# SilentStepStick-TMC2100_v11.net
KiCad netlist of a schematic drawn in EAGLE
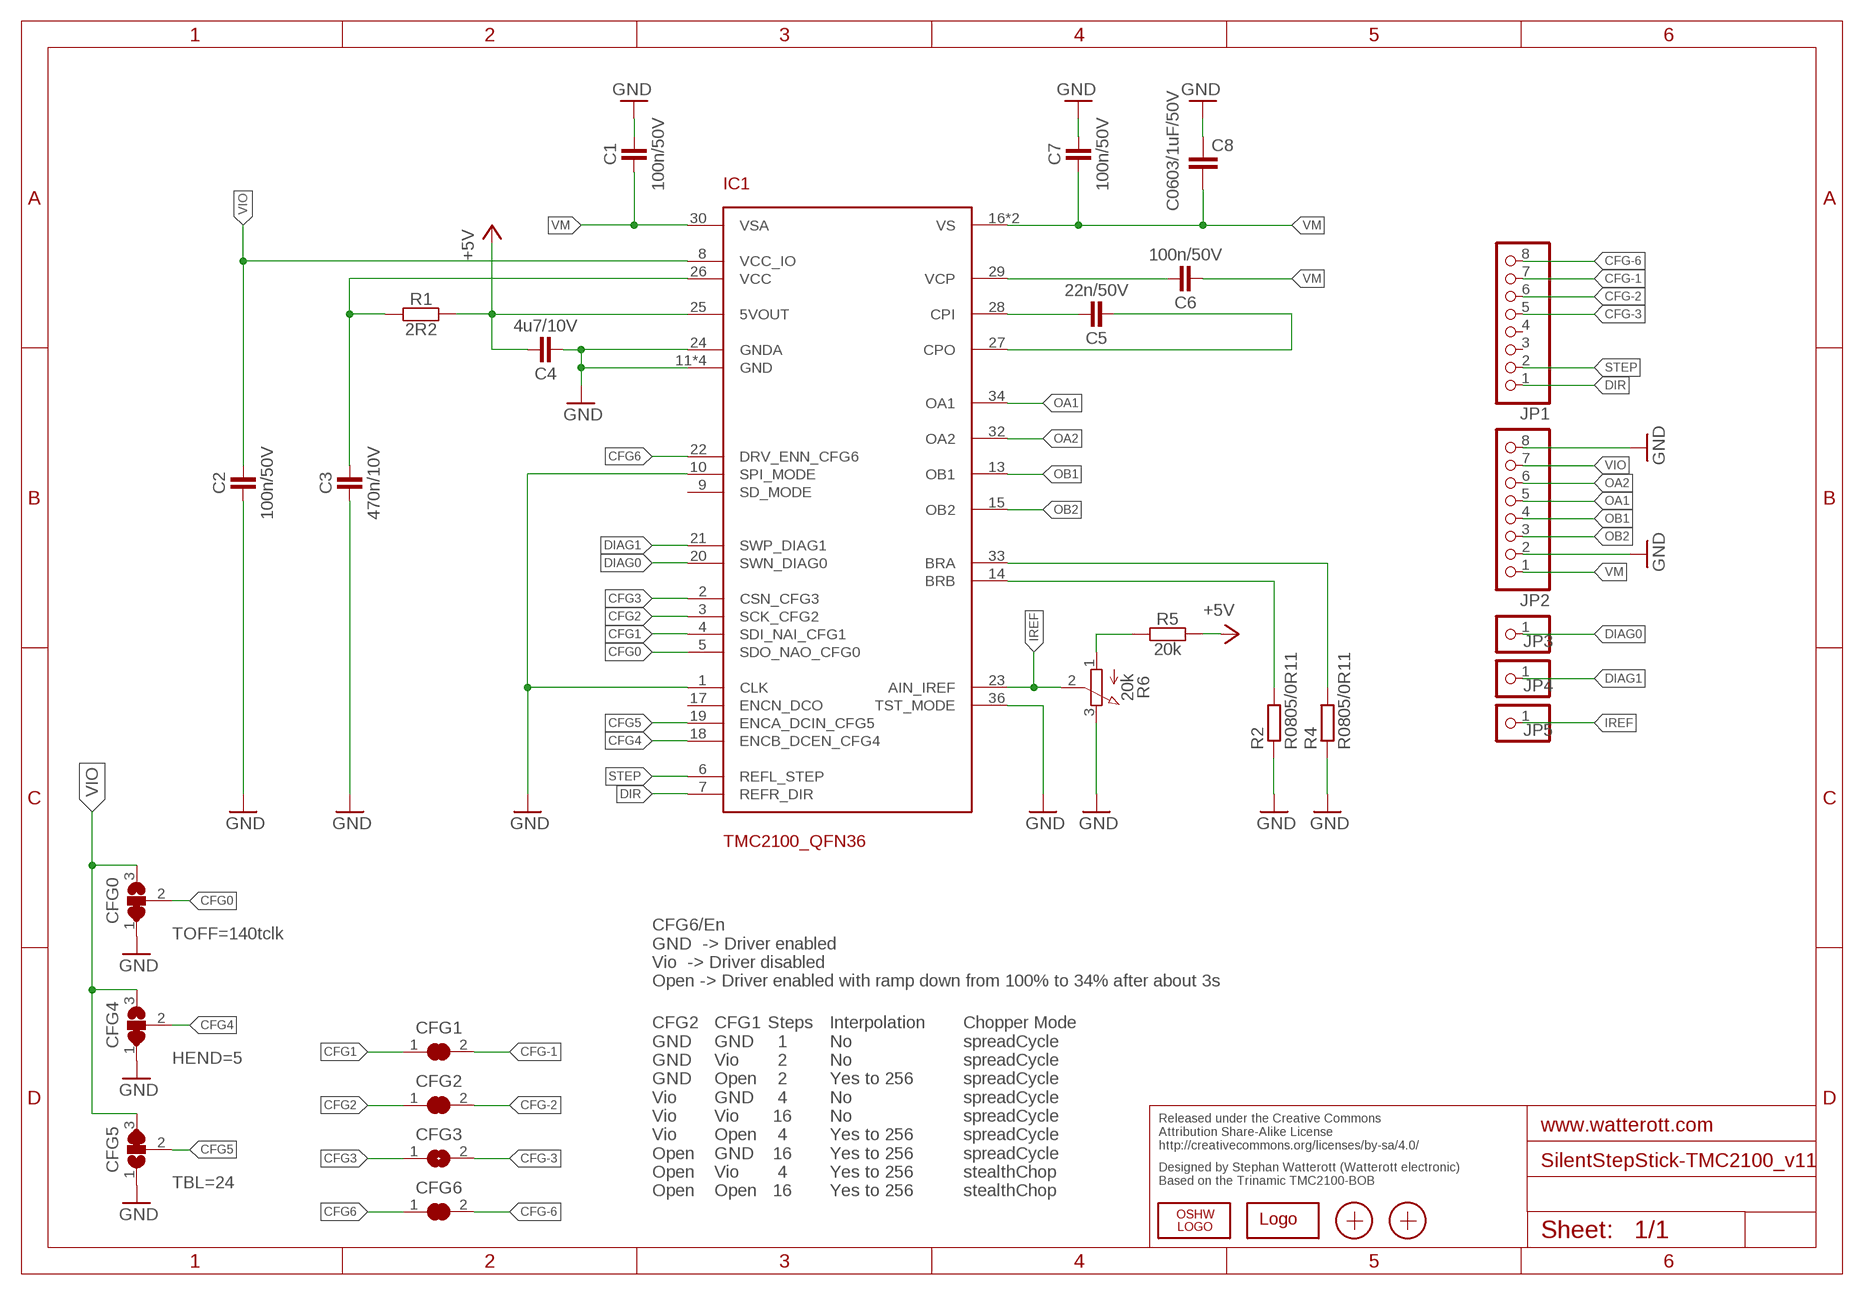
[diagram p0: schematic, sheet 1]

(export (version "E")
  (design (tool "Eeschema 10.0.6"))
  (components
    (comp (ref "C1")
      (value "100n/50V")
      (footprint "eagle-import:R0402")
      (libsource (lib "eagle-import") (part "CAPACITOR-C0402"))
    )
    (comp (ref "C2")
      (value "100n/50V")
      (footprint "eagle-import:R0402")
      (libsource (lib "eagle-import") (part "CAPACITOR-C0402"))
    )
    (comp (ref "C3")
      (value "470n/10V")
      (footprint "eagle-import:R0402")
      (libsource (lib "eagle-import") (part "CAPACITOR-C0402"))
    )
    (comp (ref "C4")
      (value "4u7/10V")
      (footprint "eagle-import:R0402")
      (libsource (lib "eagle-import") (part "CAPACITOR-C0402"))
    )
    (comp (ref "C5")
      (value "22n/50V")
      (footprint "eagle-import:R0402")
      (libsource (lib "eagle-import") (part "CAPACITOR-C0402"))
    )
    (comp (ref "C6")
      (value "100n/50V")
      (footprint "eagle-import:R0402")
      (libsource (lib "eagle-import") (part "CAPACITOR-C0402"))
    )
    (comp (ref "C7")
      (value "100n/50V")
      (footprint "eagle-import:R0402")
      (libsource (lib "eagle-import") (part "CAPACITOR-C0402"))
    )
    (comp (ref "C8")
      (value "C0603/1uF/50V")
      (footprint "eagle-import:C0603")
      (libsource (lib "eagle-import") (part "C-EUC0603"))
    )
    (comp (ref "CFG0")
      (value "JUMPER3-0201")
      (footprint "eagle-import:JUMPER3-0201")
      (libsource (lib "eagle-import") (part "JUMPER3-0201"))
    )
    (comp (ref "CFG1")
      (value "JUMPER2-0201")
      (footprint "eagle-import:JUMPER2-0201")
      (libsource (lib "eagle-import") (part "JUMPER2-0201"))
    )
    (comp (ref "CFG2")
      (value "JUMPER2-0201")
      (footprint "eagle-import:JUMPER2-0201")
      (libsource (lib "eagle-import") (part "JUMPER2-0201"))
    )
    (comp (ref "CFG3")
      (value "JUMPER2-0201")
      (footprint "eagle-import:JUMPER2-0201")
      (libsource (lib "eagle-import") (part "JUMPER2-0201"))
    )
    (comp (ref "CFG4")
      (value "JUMPER3-0201")
      (footprint "eagle-import:JUMPER3-0201")
      (libsource (lib "eagle-import") (part "JUMPER3-0201"))
    )
    (comp (ref "CFG5")
      (value "JUMPER3-0201")
      (footprint "eagle-import:JUMPER3-0201")
      (libsource (lib "eagle-import") (part "JUMPER3-0201"))
    )
    (comp (ref "CFG6")
      (value "JUMPER2-0201")
      (footprint "eagle-import:JUMPER2-0201")
      (libsource (lib "eagle-import") (part "JUMPER2-0201"))
    )
    (comp (ref "IC1")
      (value "TMC2100_QFN36")
      (footprint "eagle-import:QFN36")
      (libsource (lib "eagle-import") (part "TMC2100_QFN36"))
    )
    (comp (ref "JP1")
      (value "PINHD-1X08_2.54-S")
      (footprint "eagle-import:1X08-S")
      (libsource (lib "eagle-import") (part "PINHD-1X08_2.54-S"))
    )
    (comp (ref "JP2")
      (value "PINHD-1X08_2.54-S")
      (footprint "eagle-import:1X08-S")
      (libsource (lib "eagle-import") (part "PINHD-1X08_2.54-S"))
    )
    (comp (ref "JP3")
      (value "PINHD-1X1")
      (footprint "eagle-import:1X01")
      (libsource (lib "eagle-import") (part "PINHD-1X1"))
    )
    (comp (ref "JP4")
      (value "PINHD-1X1")
      (footprint "eagle-import:1X01")
      (libsource (lib "eagle-import") (part "PINHD-1X1"))
    )
    (comp (ref "JP5")
      (value "PINHD-1X1")
      (footprint "eagle-import:1X01")
      (libsource (lib "eagle-import") (part "PINHD-1X1"))
    )
    (comp (ref "LOGO1")
      (value "OSHW_LOGOX0070")
      (footprint "eagle-import:OSHW_6X70")
      (libsource (lib "eagle-import") (part "OSHW_LOGOX0070"))
    )
    (comp (ref "LOGO2")
      (value "LOGO-S_PLACE_M")
      (footprint "eagle-import:SPARK_TPLACE_M")
      (libsource (lib "eagle-import") (part "LOGO-S_PLACE_M"))
    )
    (comp (ref "R1")
      (value "2R2")
      (footprint "eagle-import:R0402")
      (libsource (lib "eagle-import") (part "RESISTOR-R0402"))
    )
    (comp (ref "R2")
      (value "R0805/0R11")
      (footprint "eagle-import:M0805")
      (libsource (lib "eagle-import") (part "R-EU_M0805"))
    )
    (comp (ref "R4")
      (value "R0805/0R11")
      (footprint "eagle-import:M0805")
      (libsource (lib "eagle-import") (part "R-EU_M0805"))
    )
    (comp (ref "R5")
      (value "20k")
      (footprint "eagle-import:R0402")
      (libsource (lib "eagle-import") (part "RESISTOR-R0402"))
    )
    (comp (ref "R6")
      (value "20k")
      (footprint "eagle-import:POT_EVM3R")
      (libsource (lib "eagle-import") (part "POTEVM3R"))
    )
    (comp (ref "X1")
      (value "PASSER-07")
      (footprint "eagle-import:PASSER_07MM")
      (libsource (lib "eagle-import") (part "PASSER-07"))
    )
    (comp (ref "X2")
      (value "PASSER-07")
      (footprint "eagle-import:PASSER_07MM")
      (libsource (lib "eagle-import") (part "PASSER-07"))
    )
  )
  (nets
    (net (code "1") (name "+5V") (class "Default")
      (node (ref "C4") (pin "2") (pinfunction "2_2") (pintype "passive"))
      (node (ref "IC1") (pin "25") (pinfunction "5VOUT_25") (pintype "bidirectional"))
      (node (ref "R1") (pin "2") (pinfunction "2_2") (pintype "passive"))
      (node (ref "R5") (pin "2") (pinfunction "2_2") (pintype "passive"))
    )
    (net (code "2") (name "CFG-1") (class "Default")
      (node (ref "CFG1") (pin "2") (pinfunction "2_2") (pintype "passive"))
      (node (ref "JP1") (pin "7") (pinfunction "7_7") (pintype "passive"))
    )
    (net (code "3") (name "CFG-2") (class "Default")
      (node (ref "CFG2") (pin "2") (pinfunction "2_2") (pintype "passive"))
      (node (ref "JP1") (pin "6") (pinfunction "6_6") (pintype "passive"))
    )
    (net (code "4") (name "CFG-3") (class "Default")
      (node (ref "CFG3") (pin "2") (pinfunction "2_2") (pintype "passive"))
      (node (ref "JP1") (pin "5") (pinfunction "5_5") (pintype "passive"))
    )
    (net (code "5") (name "CFG-6") (class "Default")
      (node (ref "CFG6") (pin "2") (pinfunction "2_2") (pintype "passive"))
      (node (ref "JP1") (pin "8") (pinfunction "8_8") (pintype "passive"))
    )
    (net (code "6") (name "CFG0") (class "Default")
      (node (ref "CFG0") (pin "2") (pinfunction "2_2") (pintype "passive"))
      (node (ref "IC1") (pin "5") (pinfunction "SDO_NAO_CFG0_5") (pintype "bidirectional"))
    )
    (net (code "7") (name "CFG1") (class "Default")
      (node (ref "CFG1") (pin "1") (pinfunction "1_1") (pintype "passive"))
      (node (ref "IC1") (pin "4") (pinfunction "SDI_NAI_CFG1_4") (pintype "bidirectional"))
    )
    (net (code "8") (name "CFG2") (class "Default")
      (node (ref "CFG2") (pin "1") (pinfunction "1_1") (pintype "passive"))
      (node (ref "IC1") (pin "3") (pinfunction "SCK_CFG2_3") (pintype "bidirectional"))
    )
    (net (code "9") (name "CFG3") (class "Default")
      (node (ref "CFG3") (pin "1") (pinfunction "1_1") (pintype "passive"))
      (node (ref "IC1") (pin "2") (pinfunction "CSN_CFG3_2") (pintype "bidirectional"))
    )
    (net (code "10") (name "CFG4") (class "Default")
      (node (ref "CFG4") (pin "2") (pinfunction "2_2") (pintype "passive"))
      (node (ref "IC1") (pin "18") (pinfunction "ENCB_DCEN_CFG4_18") (pintype "bidirectional"))
    )
    (net (code "11") (name "CFG5") (class "Default")
      (node (ref "CFG5") (pin "2") (pinfunction "2_2") (pintype "passive"))
      (node (ref "IC1") (pin "19") (pinfunction "ENCA_DCIN_CFG5_19") (pintype "bidirectional"))
    )
    (net (code "12") (name "CFG6") (class "Default")
      (node (ref "CFG6") (pin "1") (pinfunction "1_1") (pintype "passive"))
      (node (ref "IC1") (pin "22") (pinfunction "DRV_ENN_CFG6_22") (pintype "bidirectional"))
    )
    (net (code "13") (name "DIAG0") (class "Default")
      (node (ref "IC1") (pin "20") (pinfunction "SWN_DIAG0_20") (pintype "bidirectional"))
      (node (ref "JP3") (pin "1") (pinfunction "1_1") (pintype "passive"))
    )
    (net (code "14") (name "DIAG1") (class "Default")
      (node (ref "IC1") (pin "21") (pinfunction "SWP_DIAG1_21") (pintype "bidirectional"))
      (node (ref "JP4") (pin "1") (pinfunction "1_1") (pintype "passive"))
    )
    (net (code "15") (name "DIR") (class "Default")
      (node (ref "IC1") (pin "7") (pinfunction "REFR_DIR_7") (pintype "bidirectional"))
      (node (ref "JP1") (pin "1") (pinfunction "1_1") (pintype "passive"))
    )
    (net (code "16") (name "GND") (class "Default")
      (node (ref "C1") (pin "2") (pinfunction "2_2") (pintype "passive"))
      (node (ref "C2") (pin "1") (pinfunction "1_1") (pintype "passive"))
      (node (ref "C3") (pin "1") (pinfunction "1_1") (pintype "passive"))
      (node (ref "C4") (pin "1") (pinfunction "1_1") (pintype "passive"))
      (node (ref "C7") (pin "2") (pinfunction "2_2") (pintype "passive"))
      (node (ref "C8") (pin "2") (pinfunction "2_2") (pintype "passive"))
      (node (ref "CFG0") (pin "1") (pinfunction "1_1") (pintype "passive"))
      (node (ref "CFG4") (pin "1") (pinfunction "1_1") (pintype "passive"))
      (node (ref "CFG5") (pin "1") (pinfunction "1_1") (pintype "passive"))
      (node (ref "IC1") (pin "1") (pinfunction "CLK_1") (pintype "bidirectional"))
      (node (ref "IC1") (pin "10") (pinfunction "SPI_MODE_10") (pintype "bidirectional"))
      (node (ref "IC1") (pin "11") (pinfunction "GND_11") (pintype "bidirectional"))
      (node (ref "IC1") (pin "12") (pinfunction "GND_12") (pintype "bidirectional"))
      (node (ref "IC1") (pin "24") (pinfunction "GNDA_24") (pintype "bidirectional"))
      (node (ref "IC1") (pin "35") (pinfunction "GND_35") (pintype "bidirectional"))
      (node (ref "IC1") (pin "36") (pinfunction "TST_MODE_36") (pintype "bidirectional"))
      (node (ref "IC1") (pin "GND_PAD") (pinfunction "GND_GND_PAD") (pintype "bidirectional"))
      (node (ref "JP2") (pin "2") (pinfunction "2_2") (pintype "passive"))
      (node (ref "JP2") (pin "8") (pinfunction "8_8") (pintype "passive"))
      (node (ref "R2") (pin "1") (pinfunction "1_1") (pintype "passive"))
      (node (ref "R4") (pin "1") (pinfunction "1_1") (pintype "passive"))
      (node (ref "R6") (pin "3") (pinfunction "E_3") (pintype "passive"))
    )
    (net (code "17") (name "IREF") (class "Default")
      (node (ref "IC1") (pin "23") (pinfunction "AIN_IREF_23") (pintype "bidirectional"))
      (node (ref "JP5") (pin "1") (pinfunction "1_1") (pintype "passive"))
      (node (ref "R6") (pin "2") (pinfunction "S_2") (pintype "passive"))
    )
    (net (code "18") (name "Net-(IC1-BRA)") (class "Default")
      (node (ref "IC1") (pin "33") (pinfunction "BRA_33") (pintype "bidirectional"))
      (node (ref "R4") (pin "2") (pinfunction "2_2") (pintype "passive"))
    )
    (net (code "19") (name "Net-(IC1-BRB)") (class "Default")
      (node (ref "IC1") (pin "14") (pinfunction "BRB_14") (pintype "bidirectional"))
      (node (ref "R2") (pin "2") (pinfunction "2_2") (pintype "passive"))
    )
    (net (code "20") (name "Net-(IC1-CPI)") (class "Default")
      (node (ref "C5") (pin "2") (pinfunction "2_2") (pintype "passive"))
      (node (ref "IC1") (pin "28") (pinfunction "CPI_28") (pintype "bidirectional"))
    )
    (net (code "21") (name "Net-(IC1-CPO)") (class "Default")
      (node (ref "C5") (pin "1") (pinfunction "1_1") (pintype "passive"))
      (node (ref "IC1") (pin "27") (pinfunction "CPO_27") (pintype "bidirectional"))
    )
    (net (code "22") (name "Net-(IC1-VCC)") (class "Default")
      (node (ref "C3") (pin "2") (pinfunction "2_2") (pintype "passive"))
      (node (ref "IC1") (pin "26") (pinfunction "VCC_26") (pintype "bidirectional"))
      (node (ref "R1") (pin "1") (pinfunction "1_1") (pintype "passive"))
    )
    (net (code "23") (name "Net-(IC1-VCP)") (class "Default")
      (node (ref "C6") (pin "2") (pinfunction "2_2") (pintype "passive"))
      (node (ref "IC1") (pin "29") (pinfunction "VCP_29") (pintype "bidirectional"))
    )
    (net (code "24") (name "Net-(R6-A)") (class "Default")
      (node (ref "R5") (pin "1") (pinfunction "1_1") (pintype "passive"))
      (node (ref "R6") (pin "1") (pinfunction "A_1") (pintype "passive"))
    )
    (net (code "25") (name "OA1") (class "Default")
      (node (ref "IC1") (pin "34") (pinfunction "OA1_34") (pintype "bidirectional"))
      (node (ref "JP2") (pin "5") (pinfunction "5_5") (pintype "passive"))
    )
    (net (code "26") (name "OA2") (class "Default")
      (node (ref "IC1") (pin "32") (pinfunction "OA2_32") (pintype "bidirectional"))
      (node (ref "JP2") (pin "6") (pinfunction "6_6") (pintype "passive"))
    )
    (net (code "27") (name "OB1") (class "Default")
      (node (ref "IC1") (pin "13") (pinfunction "OB1_13") (pintype "bidirectional"))
      (node (ref "JP2") (pin "4") (pinfunction "4_4") (pintype "passive"))
    )
    (net (code "28") (name "OB2") (class "Default")
      (node (ref "IC1") (pin "15") (pinfunction "OB2_15") (pintype "bidirectional"))
      (node (ref "JP2") (pin "3") (pinfunction "3_3") (pintype "passive"))
    )
    (net (code "29") (name "STEP") (class "Default")
      (node (ref "IC1") (pin "6") (pinfunction "REFL_STEP_6") (pintype "bidirectional"))
      (node (ref "JP1") (pin "2") (pinfunction "2_2") (pintype "passive"))
    )
    (net (code "30") (name "VIO") (class "Default")
      (node (ref "C2") (pin "2") (pinfunction "2_2") (pintype "passive"))
      (node (ref "CFG0") (pin "3") (pinfunction "3_3") (pintype "passive"))
      (node (ref "CFG4") (pin "3") (pinfunction "3_3") (pintype "passive"))
      (node (ref "CFG5") (pin "3") (pinfunction "3_3") (pintype "passive"))
      (node (ref "IC1") (pin "8") (pinfunction "VCC_IO_8") (pintype "bidirectional"))
      (node (ref "JP2") (pin "7") (pinfunction "7_7") (pintype "passive"))
    )
    (net (code "31") (name "VM") (class "Default")
      (node (ref "C1") (pin "1") (pinfunction "1_1") (pintype "passive"))
      (node (ref "C6") (pin "1") (pinfunction "1_1") (pintype "passive"))
      (node (ref "C7") (pin "1") (pinfunction "1_1") (pintype "passive"))
      (node (ref "C8") (pin "1") (pinfunction "1_1") (pintype "passive"))
      (node (ref "IC1") (pin "16") (pinfunction "VS_16") (pintype "bidirectional"))
      (node (ref "IC1") (pin "30") (pinfunction "VSA_30") (pintype "bidirectional"))
      (node (ref "IC1") (pin "31") (pinfunction "VS_31") (pintype "bidirectional"))
      (node (ref "JP2") (pin "1") (pinfunction "1_1") (pintype "passive"))
    )
    (net (code "32") (name "unconnected-(IC1-ENCN_DCO-Pad17)") (class "Default")
      (node (ref "IC1") (pin "17") (pinfunction "ENCN_DCO_17") (pintype "bidirectional"))
    )
    (net (code "33") (name "unconnected-(IC1-SD_MODE-Pad9)") (class "Default")
      (node (ref "IC1") (pin "9") (pinfunction "SD_MODE_9") (pintype "bidirectional"))
    )
    (net (code "34") (name "unconnected-(JP1-Pad3)") (class "Default")
      (node (ref "JP1") (pin "3") (pinfunction "3_3") (pintype "passive"))
    )
    (net (code "35") (name "unconnected-(JP1-Pad4)") (class "Default")
      (node (ref "JP1") (pin "4") (pinfunction "4_4") (pintype "passive"))
    )
  )
)
